# untitled.net
KiCad netlist of a schematic drawn in EAGLE
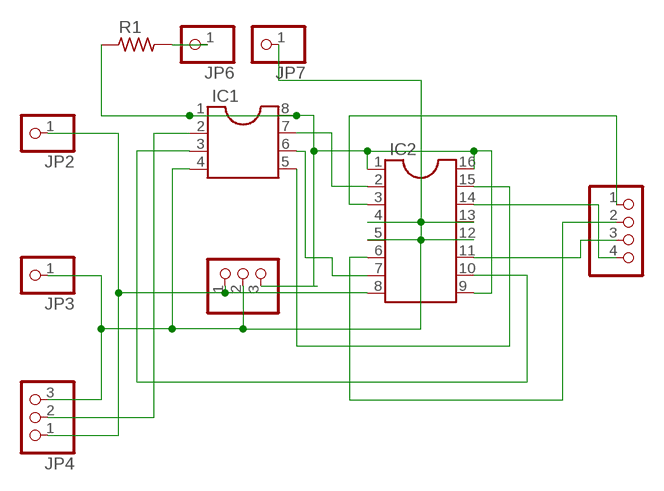
[diagram p0: schematic, sheet 1]

(export (version "E")
  (design (tool "Eeschema 10.0.6"))
  (components
    (comp (ref "IC1")
      (value "DIL8S")
      (footprint "eagle-import:SOCKET-08")
      (libsource (lib "eagle-import") (part "DIL8S"))
    )
    (comp (ref "IC2")
      (value "DIL16S")
      (footprint "eagle-import:SOCKET-16")
      (libsource (lib "eagle-import") (part "DIL16S"))
    )
    (comp (ref "JP1")
      (value "PINHD-1X4")
      (footprint "eagle-import:1X04")
      (libsource (lib "eagle-import") (part "PINHD-1X4"))
    )
    (comp (ref "JP2")
      (value "PINHD-1X1")
      (footprint "eagle-import:1X01")
      (libsource (lib "eagle-import") (part "PINHD-1X1"))
    )
    (comp (ref "JP3")
      (value "PINHD-1X1")
      (footprint "eagle-import:1X01")
      (libsource (lib "eagle-import") (part "PINHD-1X1"))
    )
    (comp (ref "JP4")
      (value "PINHD-1X3")
      (footprint "eagle-import:1X03")
      (libsource (lib "eagle-import") (part "PINHD-1X3"))
    )
    (comp (ref "JP5")
      (value "PINHD-1X3")
      (footprint "eagle-import:1X03")
      (libsource (lib "eagle-import") (part "PINHD-1X3"))
    )
    (comp (ref "JP6")
      (value "PINHD-1X1")
      (footprint "eagle-import:1X01")
      (libsource (lib "eagle-import") (part "PINHD-1X1"))
    )
    (comp (ref "JP7")
      (value "PINHD-1X1")
      (footprint "eagle-import:1X01")
      (libsource (lib "eagle-import") (part "PINHD-1X1"))
    )
    (comp (ref "R1")
      (value "RC-MASTER-SMD_R_0603MP")
      (footprint "eagle-import:RC-MASTER-SMD_R0603MP")
      (libsource (lib "eagle-import") (part "RC-MASTER-SMD_R_0603MP"))
    )
  )
  (nets
    (net (code "1") (name "Net-(IC1-Pad1)") (class "Default")
      (node (ref "IC1") (pin "1") (pinfunction "1_1") (pintype "passive"))
      (node (ref "IC1") (pin "8") (pinfunction "8_8") (pintype "passive"))
      (node (ref "IC2") (pin "1") (pinfunction "1_1") (pintype "passive"))
      (node (ref "IC2") (pin "16") (pinfunction "16_16") (pintype "passive"))
      (node (ref "IC2") (pin "9") (pinfunction "9_9") (pintype "passive"))
      (node (ref "JP5") (pin "3") (pinfunction "3_3") (pintype "passive"))
      (node (ref "R1") (pin "1") (pinfunction "1_1") (pintype "passive"))
    )
    (net (code "2") (name "Net-(IC1-Pad2)") (class "Default")
      (node (ref "IC1") (pin "2") (pinfunction "2_2") (pintype "passive"))
      (node (ref "JP4") (pin "2") (pinfunction "2_2") (pintype "passive"))
    )
    (net (code "3") (name "Net-(IC1-Pad3)") (class "Default")
      (node (ref "IC1") (pin "3") (pinfunction "3_3") (pintype "passive"))
      (node (ref "IC2") (pin "10") (pinfunction "10_10") (pintype "passive"))
    )
    (net (code "4") (name "Net-(IC1-Pad4)") (class "Default")
      (node (ref "IC1") (pin "4") (pinfunction "4_4") (pintype "passive"))
      (node (ref "IC2") (pin "12") (pinfunction "12_12") (pintype "passive"))
      (node (ref "IC2") (pin "13") (pinfunction "13_13") (pintype "passive"))
      (node (ref "IC2") (pin "4") (pinfunction "4_4") (pintype "passive"))
      (node (ref "IC2") (pin "5") (pinfunction "5_5") (pintype "passive"))
      (node (ref "JP3") (pin "1") (pinfunction "1_1") (pintype "passive"))
      (node (ref "JP4") (pin "3") (pinfunction "3_3") (pintype "passive"))
      (node (ref "JP5") (pin "2") (pinfunction "2_2") (pintype "passive"))
      (node (ref "JP7") (pin "1") (pinfunction "1_1") (pintype "passive"))
    )
    (net (code "5") (name "Net-(IC1-Pad5)") (class "Default")
      (node (ref "IC1") (pin "5") (pinfunction "5_5") (pintype "passive"))
      (node (ref "IC2") (pin "15") (pinfunction "15_15") (pintype "passive"))
    )
    (net (code "6") (name "Net-(IC1-Pad6)") (class "Default")
      (node (ref "IC1") (pin "6") (pinfunction "6_6") (pintype "passive"))
      (node (ref "IC2") (pin "7") (pinfunction "7_7") (pintype "passive"))
    )
    (net (code "7") (name "Net-(IC1-Pad7)") (class "Default")
      (node (ref "IC1") (pin "7") (pinfunction "7_7") (pintype "passive"))
      (node (ref "IC2") (pin "2") (pinfunction "2_2") (pintype "passive"))
    )
    (net (code "8") (name "Net-(IC2-Pad3)") (class "Default")
      (node (ref "IC2") (pin "3") (pinfunction "3_3") (pintype "passive"))
      (node (ref "JP1") (pin "1") (pinfunction "1_1") (pintype "passive"))
    )
    (net (code "9") (name "Net-(IC2-Pad6)") (class "Default")
      (node (ref "IC2") (pin "6") (pinfunction "6_6") (pintype "passive"))
      (node (ref "JP1") (pin "2") (pinfunction "2_2") (pintype "passive"))
    )
    (net (code "10") (name "Net-(IC2-Pad8)") (class "Default")
      (node (ref "IC2") (pin "8") (pinfunction "8_8") (pintype "passive"))
      (node (ref "JP2") (pin "1") (pinfunction "1_1") (pintype "passive"))
      (node (ref "JP4") (pin "1") (pinfunction "1_1") (pintype "passive"))
      (node (ref "JP5") (pin "1") (pinfunction "1_1") (pintype "passive"))
    )
    (net (code "11") (name "Net-(IC2-Pad11)") (class "Default")
      (node (ref "IC2") (pin "11") (pinfunction "11_11") (pintype "passive"))
      (node (ref "JP1") (pin "3") (pinfunction "3_3") (pintype "passive"))
    )
    (net (code "12") (name "Net-(IC2-Pad14)") (class "Default")
      (node (ref "IC2") (pin "14") (pinfunction "14_14") (pintype "passive"))
      (node (ref "JP1") (pin "4") (pinfunction "4_4") (pintype "passive"))
    )
    (net (code "13") (name "Net-(JP6-Pad1)") (class "Default")
      (node (ref "JP6") (pin "1") (pinfunction "1_1") (pintype "passive"))
      (node (ref "R1") (pin "2") (pinfunction "2_2") (pintype "passive"))
    )
  )
)
